# SCH_Syntheseproject_2022-10-14.net
KiCad netlist of a schematic drawn in EasyEDA
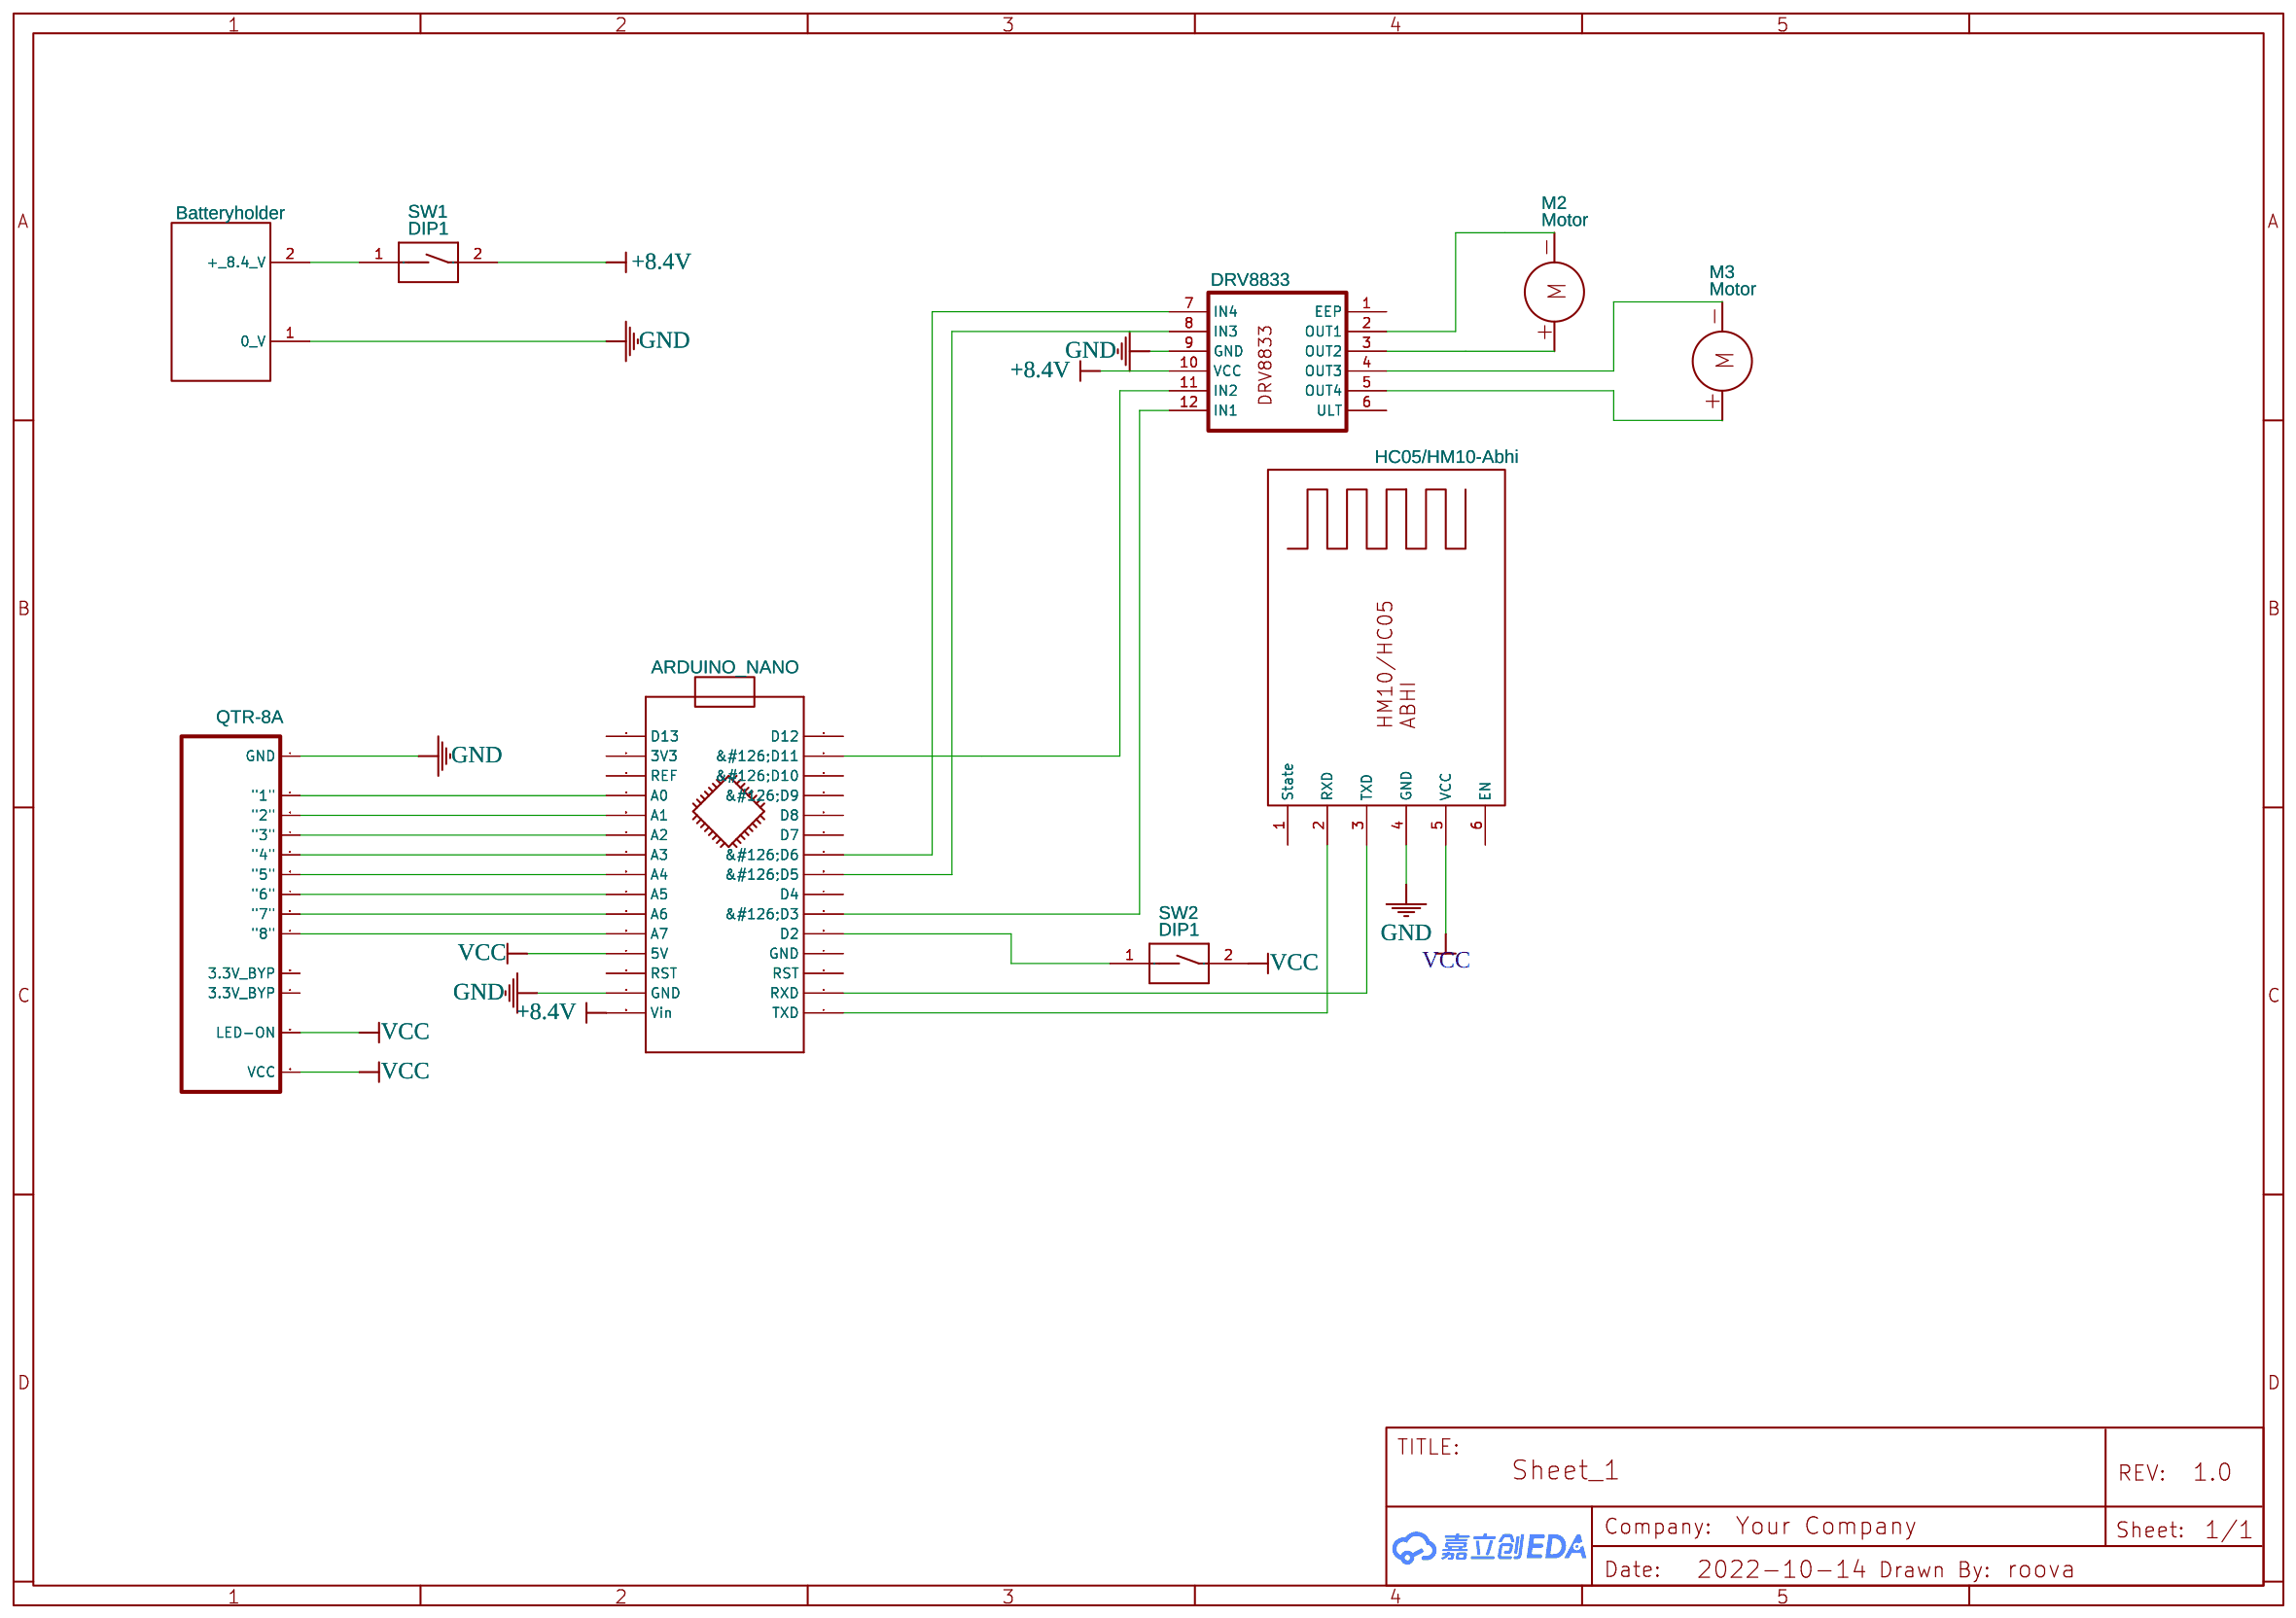
[diagram p0: schematic sheet]

(export (version "E")
  (design (tool "Eeschema 10.0.6"))
  (components
    (comp (ref "ARDUINO_NANO")
      (value "ARDUINO-NANO_V3")
      (fields (field (name "BOM_Manufacturer Part") "ARDUINO-NANO_AK"))
      (libsource (lib "") (part "ARDUINO-NANO_V3"))
    )
    (comp (ref "M2") (value "Motor") (libsource (lib "") (part "Motor")))
    (comp (ref "M3") (value "Motor") (libsource (lib "") (part "Motor")))
    (comp (ref "SW1")
      (value "DIP1")
      (fields
        (field (name "BOM_Manufacturer Part") "A6TN-1101")
        (field (name "BOM_Supplier Part") "Z12167-ND")
      )
      (libsource (lib "") (part "DIP1"))
    )
    (comp (ref "SW2")
      (value "DIP1")
      (fields
        (field (name "BOM_Manufacturer Part") "A6TN-1101")
        (field (name "BOM_Supplier Part") "Z12167-ND")
      )
      (libsource (lib "") (part "DIP1"))
    )
    (comp (ref "U1") (value "DRV8833") (libsource (lib "") (part "DRV8833 (NO ORIGINAL)")))
    (comp (ref "U2")
      (value "QTR-8A")
      (fields (field (name "BOM_Supplier Part") "960"))
      (libsource (lib "") (part "QTR-8A"))
    )
    (comp (ref "U3") (value "HC05/HM10-Abhi") (libsource (lib "") (part "HC05/HM10-Abhi")))
    (comp (ref "U4") (value "Batteryholder") (libsource (lib "") (part "Batteryholder")))
  )
  (nets
    (net (code "1") (name "+8.4V") (class "Default")
      (node (ref "ARDUINO_NANO") (pin "30") (pinfunction "Vin_30") (pintype "unspecified"))
      (node (ref "SW1") (pin "2") (pinfunction "2_2") (pintype "unspecified"))
      (node (ref "U1") (pin "10") (pinfunction "VCC_10") (pintype "unspecified"))
    )
    (net (code "2") (name "GND") (class "Default")
      (node (ref "ARDUINO_NANO") (pin "29") (pinfunction "GND_29") (pintype "unspecified"))
      (node (ref "U1") (pin "9") (pinfunction "GND_9") (pintype "unspecified"))
      (node (ref "U2") (pin "1") (pinfunction "GND_1") (pintype "unspecified"))
      (node (ref "U3") (pin "4") (pinfunction "GND_4") (pintype "unspecified"))
      (node (ref "U4") (pin "1") (pinfunction "0_V_1") (pintype "unspecified"))
    )
    (net (code "3") (name "Net-(ARDUINO_NANO-&#126;D3)") (class "Default")
      (node (ref "ARDUINO_NANO") (pin "6") (pinfunction "&#126;D3_6") (pintype "unspecified"))
      (node (ref "U1") (pin "12") (pinfunction "IN1_12") (pintype "unspecified"))
    )
    (net (code "4") (name "Net-(ARDUINO_NANO-&#126;D5)") (class "Default")
      (node (ref "ARDUINO_NANO") (pin "8") (pinfunction "&#126;D5_8") (pintype "unspecified"))
      (node (ref "U1") (pin "8") (pinfunction "IN3_8") (pintype "unspecified"))
    )
    (net (code "5") (name "Net-(ARDUINO_NANO-&#126;D6)") (class "Default")
      (node (ref "ARDUINO_NANO") (pin "9") (pinfunction "&#126;D6_9") (pintype "unspecified"))
      (node (ref "U1") (pin "7") (pinfunction "IN4_7") (pintype "unspecified"))
    )
    (net (code "6") (name "Net-(ARDUINO_NANO-&#126;D11)") (class "Default")
      (node (ref "ARDUINO_NANO") (pin "14") (pinfunction "&#126;D11_14") (pintype "unspecified"))
      (node (ref "U1") (pin "11") (pinfunction "IN2_11") (pintype "unspecified"))
    )
    (net (code "7") (name "Net-(ARDUINO_NANO-A0)") (class "Default")
      (node (ref "ARDUINO_NANO") (pin "19") (pinfunction "A0_19") (pintype "unspecified"))
      (node (ref "U2") (pin "2") (pinfunction "\"1\"_2") (pintype "unspecified"))
    )
    (net (code "8") (name "Net-(ARDUINO_NANO-A1)") (class "Default")
      (node (ref "ARDUINO_NANO") (pin "20") (pinfunction "A1_20") (pintype "unspecified"))
      (node (ref "U2") (pin "3") (pinfunction "\"2\"_3") (pintype "unspecified"))
    )
    (net (code "9") (name "Net-(ARDUINO_NANO-A2)") (class "Default")
      (node (ref "ARDUINO_NANO") (pin "21") (pinfunction "A2_21") (pintype "unspecified"))
      (node (ref "U2") (pin "4") (pinfunction "\"3\"_4") (pintype "unspecified"))
    )
    (net (code "10") (name "Net-(ARDUINO_NANO-A3)") (class "Default")
      (node (ref "ARDUINO_NANO") (pin "22") (pinfunction "A3_22") (pintype "unspecified"))
      (node (ref "U2") (pin "5") (pinfunction "\"4\"_5") (pintype "unspecified"))
    )
    (net (code "11") (name "Net-(ARDUINO_NANO-A4)") (class "Default")
      (node (ref "ARDUINO_NANO") (pin "23") (pinfunction "A4_23") (pintype "unspecified"))
      (node (ref "U2") (pin "6") (pinfunction "\"5\"_6") (pintype "unspecified"))
    )
    (net (code "12") (name "Net-(ARDUINO_NANO-A5)") (class "Default")
      (node (ref "ARDUINO_NANO") (pin "24") (pinfunction "A5_24") (pintype "unspecified"))
      (node (ref "U2") (pin "7") (pinfunction "\"6\"_7") (pintype "unspecified"))
    )
    (net (code "13") (name "Net-(ARDUINO_NANO-A6)") (class "Default")
      (node (ref "ARDUINO_NANO") (pin "25") (pinfunction "A6_25") (pintype "unspecified"))
      (node (ref "U2") (pin "8") (pinfunction "\"7\"_8") (pintype "unspecified"))
    )
    (net (code "14") (name "Net-(ARDUINO_NANO-A7)") (class "Default")
      (node (ref "ARDUINO_NANO") (pin "26") (pinfunction "A7_26") (pintype "unspecified"))
      (node (ref "U2") (pin "9") (pinfunction "\"8\"_9") (pintype "unspecified"))
    )
    (net (code "15") (name "Net-(ARDUINO_NANO-D2)") (class "Default")
      (node (ref "ARDUINO_NANO") (pin "5") (pinfunction "D2_5") (pintype "unspecified"))
      (node (ref "SW2") (pin "1") (pinfunction "1_1") (pintype "unspecified"))
    )
    (net (code "16") (name "Net-(ARDUINO_NANO-RXD)") (class "Default")
      (node (ref "ARDUINO_NANO") (pin "2") (pinfunction "RXD_2") (pintype "unspecified"))
      (node (ref "U3") (pin "3") (pinfunction "TXD_3") (pintype "unspecified"))
    )
    (net (code "17") (name "Net-(ARDUINO_NANO-TXD)") (class "Default")
      (node (ref "ARDUINO_NANO") (pin "1") (pinfunction "TXD_1") (pintype "unspecified"))
      (node (ref "U3") (pin "2") (pinfunction "RXD_2") (pintype "unspecified"))
    )
    (net (code "18") (name "Net-(U4-+_8.4_V)") (class "Default")
      (node (ref "SW1") (pin "1") (pinfunction "1_1") (pintype "unspecified"))
      (node (ref "U4") (pin "2") (pinfunction "+_8.4_V_2") (pintype "unspecified"))
    )
    (net (code "19") (name "VCC") (class "Default")
      (node (ref "ARDUINO_NANO") (pin "27") (pinfunction "5V_27") (pintype "unspecified"))
      (node (ref "SW2") (pin "2") (pinfunction "2_2") (pintype "unspecified"))
      (node (ref "U2") (pin "12") (pinfunction "LED-ON_12") (pintype "unspecified"))
      (node (ref "U3") (pin "5") (pinfunction "VCC_5") (pintype "unspecified"))
    )
    (net (code "20") (name "unconnected-(ARDUINO_NANO-&#126;D9-Pad12)") (class "Default")
      (node (ref "ARDUINO_NANO") (pin "12") (pinfunction "&#126;D9_12") (pintype "unspecified"))
    )
    (net (code "21") (name "unconnected-(ARDUINO_NANO-&#126;D10-Pad13)") (class "Default")
      (node (ref "ARDUINO_NANO") (pin "13") (pinfunction "&#126;D10_13") (pintype "unspecified"))
    )
    (net (code "22") (name "unconnected-(ARDUINO_NANO-3V3-Pad17)") (class "Default")
      (node (ref "ARDUINO_NANO") (pin "17") (pinfunction "3V3_17") (pintype "unspecified"))
    )
    (net (code "23") (name "unconnected-(ARDUINO_NANO-D4-Pad7)") (class "Default")
      (node (ref "ARDUINO_NANO") (pin "7") (pinfunction "D4_7") (pintype "unspecified"))
    )
    (net (code "24") (name "unconnected-(ARDUINO_NANO-D7-Pad10)") (class "Default")
      (node (ref "ARDUINO_NANO") (pin "10") (pinfunction "D7_10") (pintype "unspecified"))
    )
    (net (code "25") (name "unconnected-(ARDUINO_NANO-D8-Pad11)") (class "Default")
      (node (ref "ARDUINO_NANO") (pin "11") (pinfunction "D8_11") (pintype "unspecified"))
    )
    (net (code "26") (name "unconnected-(ARDUINO_NANO-D12-Pad15)") (class "Default")
      (node (ref "ARDUINO_NANO") (pin "15") (pinfunction "D12_15") (pintype "unspecified"))
    )
    (net (code "27") (name "unconnected-(ARDUINO_NANO-D13-Pad16)") (class "Default")
      (node (ref "ARDUINO_NANO") (pin "16") (pinfunction "D13_16") (pintype "unspecified"))
    )
    (net (code "28") (name "unconnected-(ARDUINO_NANO-GND-Pad4)") (class "Default")
      (node (ref "ARDUINO_NANO") (pin "4") (pinfunction "GND_4") (pintype "unspecified"))
    )
    (net (code "29") (name "unconnected-(ARDUINO_NANO-REF-Pad18)") (class "Default")
      (node (ref "ARDUINO_NANO") (pin "18") (pinfunction "REF_18") (pintype "unspecified"))
    )
    (net (code "30") (name "unconnected-(ARDUINO_NANO-RST-Pad3)") (class "Default")
      (node (ref "ARDUINO_NANO") (pin "3") (pinfunction "RST_3") (pintype "unspecified"))
    )
    (net (code "31") (name "unconnected-(ARDUINO_NANO-RST-Pad28)") (class "Default")
      (node (ref "ARDUINO_NANO") (pin "28") (pinfunction "RST_28") (pintype "unspecified"))
    )
    (net (code "32") (name "unconnected-(U1-EEP-Pad1)") (class "Default")
      (node (ref "U1") (pin "1") (pinfunction "EEP_1") (pintype "unspecified"))
    )
    (net (code "33") (name "unconnected-(U1-OUT1-Pad2)") (class "Default")
      (node (ref "U1") (pin "2") (pinfunction "OUT1_2") (pintype "unspecified"))
    )
    (net (code "34") (name "unconnected-(U1-OUT2-Pad3)") (class "Default")
      (node (ref "U1") (pin "3") (pinfunction "OUT2_3") (pintype "unspecified"))
    )
    (net (code "35") (name "unconnected-(U1-OUT3-Pad4)") (class "Default")
      (node (ref "U1") (pin "4") (pinfunction "OUT3_4") (pintype "unspecified"))
    )
    (net (code "36") (name "unconnected-(U1-OUT4-Pad5)") (class "Default")
      (node (ref "U1") (pin "5") (pinfunction "OUT4_5") (pintype "unspecified"))
    )
    (net (code "37") (name "unconnected-(U1-ULT-Pad6)") (class "Default")
      (node (ref "U1") (pin "6") (pinfunction "ULT_6") (pintype "unspecified"))
    )
    (net (code "38") (name "unconnected-(U2-3.3V_BYP-Pad10)") (class "Default")
      (node (ref "U2") (pin "10") (pinfunction "3.3V_BYP_10") (pintype "unspecified"))
    )
    (net (code "39") (name "unconnected-(U2-3.3V_BYP-Pad11)") (class "Default")
      (node (ref "U2") (pin "11") (pinfunction "3.3V_BYP_11") (pintype "unspecified"))
    )
    (net (code "40") (name "unconnected-(U3-EN-Pad6)") (class "Default")
      (node (ref "U3") (pin "6") (pinfunction "EN_6") (pintype "unspecified"))
    )
    (net (code "41") (name "unconnected-(U3-State-Pad1)") (class "Default")
      (node (ref "U3") (pin "1") (pinfunction "State_1") (pintype "unspecified"))
    )
  )
)
